# Signal_imputs.net
KiCad netlist of a schematic drawn in Altium Designer
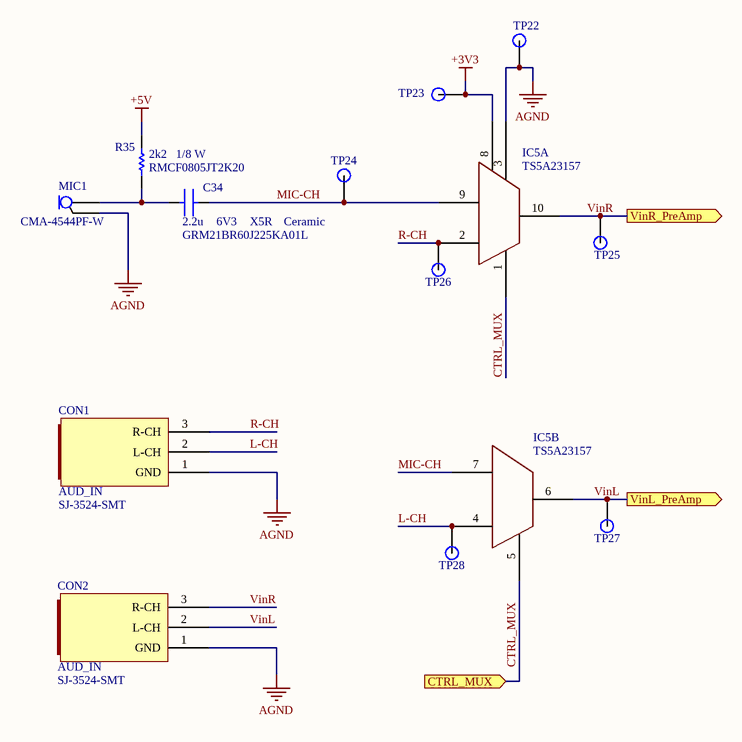
[diagram p0: Signal_imputs.SchDoc]

(export (version "E")
  (design (tool "Eeschema 10.0.6"))
  (components
    (comp (ref "C34")
      (value "2.2u 6V3 X5R Ceramic")
      (footprint "C_0805")
      (description "Capacitor")
      (fields
        (field (name "C") "2.2u")
        (field (name "V") "6V3")
        (field (name "TEMP COEF") "X5R")
        (field (name "PART NUMBER") "GRM21BR60J225KA01L")
        (field (name "MATERIAL") "Ceramic")
      )
      (libsource (lib "TDII_Lib_V2") (part "Cap1"))
    )
    (comp (ref "CON1")
      (value "AUD_IN")
      (footprint "AUDIO_JACK 3.5mm SMD")
      (fields (field (name "PART NUMBER") "SJ-3524-SMT"))
      (libsource (lib "TDII_Lib_V2") (part "Jack_1"))
    )
    (comp (ref "CON2")
      (value "AUD_IN")
      (footprint "AUDIO_JACK 3.5mm SMD")
      (fields (field (name "PART NUMBER") "SJ-3524-SMT"))
      (libsource (lib "TDII_Lib_V2") (part "Jack_1"))
    )
    (comp (ref "IC5")
      (value "TS5A23157")
      (footprint "TSSOP50P490X110-10N")
      (description "Analog Switch")
      (libsource (lib "TDII_Lib_V2") (part "A_SW_2x2{colon}1_VSSOP"))
    )
    (comp (ref "MIC1")
      (value "Mic")
      (footprint "MIC_CMA-4544PF-W")
      (description "Microfono")
      (fields (field (name "PART NUMBER") "CMA-4544PF-W"))
      (libsource (lib "TDII_Lib_V2") (part "Mic"))
    )
    (comp (ref "R35")
      (value "2k2")
      (footprint "R_0805")
      (description "Resistor")
      (fields
        (field (name "PART NUMBER") "RMCF0805JT2K20")
        (field (name "POWER") "1/8 W")
        (field (name "Comment") "2k2 1/8W")
      )
      (libsource (lib "TDII_Lib_V2") (part "Res1"))
    )
    (comp (ref "TP22")
      (value "TP")
      (footprint "TP")
      (description "Test Point")
      (libsource (lib "LituLib") (part "Test Point"))
    )
    (comp (ref "TP23")
      (value "TP")
      (footprint "TP")
      (description "Test Point")
      (libsource (lib "LituLib") (part "Test Point"))
    )
    (comp (ref "TP24")
      (value "TP")
      (footprint "TP")
      (description "Test Point")
      (libsource (lib "LituLib") (part "Test Point"))
    )
    (comp (ref "TP25")
      (value "TP")
      (footprint "TP")
      (description "Test Point")
      (libsource (lib "LituLib") (part "Test Point"))
    )
    (comp (ref "TP26")
      (value "TP")
      (footprint "TP")
      (description "Test Point")
      (libsource (lib "LituLib") (part "Test Point"))
    )
    (comp (ref "TP27")
      (value "TP")
      (footprint "TP")
      (description "Test Point")
      (libsource (lib "LituLib") (part "Test Point"))
    )
    (comp (ref "TP28")
      (value "TP")
      (footprint "TP")
      (description "Test Point")
      (libsource (lib "LituLib") (part "Test Point"))
    )
  )
  (nets
    (net (code "1") (name "+3V3") (class "Default")
      (node (ref "IC5") (pin "8") (pinfunction "VDD_8") (pintype "passive"))
      (node (ref "TP23") (pin "1") (pinfunction "1_1") (pintype "passive"))
    )
    (net (code "2") (name "+5V") (class "Default")
      (node (ref "R35") (pin "2") (pinfunction "2_2") (pintype "passive"))
    )
    (net (code "3") (name "/CTRL_MUX") (class "Default")
      (node (ref "IC5") (pin "1") (pinfunction "IN1_1") (pintype "passive"))
      (node (ref "IC5") (pin "5") (pinfunction "IN2_5") (pintype "passive"))
    )
    (net (code "4") (name "/L-CH") (class "Default")
      (node (ref "CON1") (pin "2") (pinfunction "L-CH_2") (pintype "passive"))
      (node (ref "IC5") (pin "4") (pinfunction "NO2_4") (pintype "passive"))
      (node (ref "TP28") (pin "1") (pinfunction "1_1") (pintype "passive"))
    )
    (net (code "5") (name "/MIC-CH") (class "Default")
      (node (ref "C34") (pin "2") (pinfunction "2_2") (pintype "passive"))
      (node (ref "IC5") (pin "7") (pinfunction "NC2_7") (pintype "passive"))
      (node (ref "IC5") (pin "9") (pinfunction "NC1_9") (pintype "passive"))
      (node (ref "TP24") (pin "1") (pinfunction "1_1") (pintype "passive"))
    )
    (net (code "6") (name "/R-CH") (class "Default")
      (node (ref "CON1") (pin "3") (pinfunction "R-CH_3") (pintype "passive"))
      (node (ref "IC5") (pin "2") (pinfunction "NO1_2") (pintype "passive"))
      (node (ref "TP26") (pin "1") (pinfunction "1_1") (pintype "passive"))
    )
    (net (code "7") (name "/VinL") (class "Default")
      (node (ref "CON2") (pin "2") (pinfunction "L-CH_2") (pintype "passive"))
      (node (ref "IC5") (pin "6") (pinfunction "COM2_6") (pintype "passive"))
      (node (ref "TP27") (pin "1") (pinfunction "1_1") (pintype "passive"))
    )
    (net (code "8") (name "/VinR") (class "Default")
      (node (ref "CON2") (pin "3") (pinfunction "R-CH_3") (pintype "passive"))
      (node (ref "IC5") (pin "10") (pinfunction "COM1_10") (pintype "passive"))
      (node (ref "TP25") (pin "1") (pinfunction "1_1") (pintype "passive"))
    )
    (net (code "9") (name "AGND") (class "Default")
      (node (ref "CON1") (pin "1") (pinfunction "GND_1") (pintype "passive"))
      (node (ref "CON2") (pin "1") (pinfunction "GND_1") (pintype "passive"))
      (node (ref "IC5") (pin "3") (pinfunction "DGND_3") (pintype "passive"))
      (node (ref "MIC1") (pin "2") (pinfunction "2_2") (pintype "passive"))
      (node (ref "TP22") (pin "1") (pinfunction "1_1") (pintype "passive"))
    )
    (net (code "10") (name "Net-(C34-Pad1)") (class "Default")
      (node (ref "C34") (pin "1") (pinfunction "1_1") (pintype "passive"))
      (node (ref "MIC1") (pin "1") (pinfunction "1_1") (pintype "passive"))
      (node (ref "R35") (pin "1") (pinfunction "1_1") (pintype "passive"))
    )
  )
)
